# Mirror_Schematic.net
KiCad netlist of a schematic drawn in Altium Designer
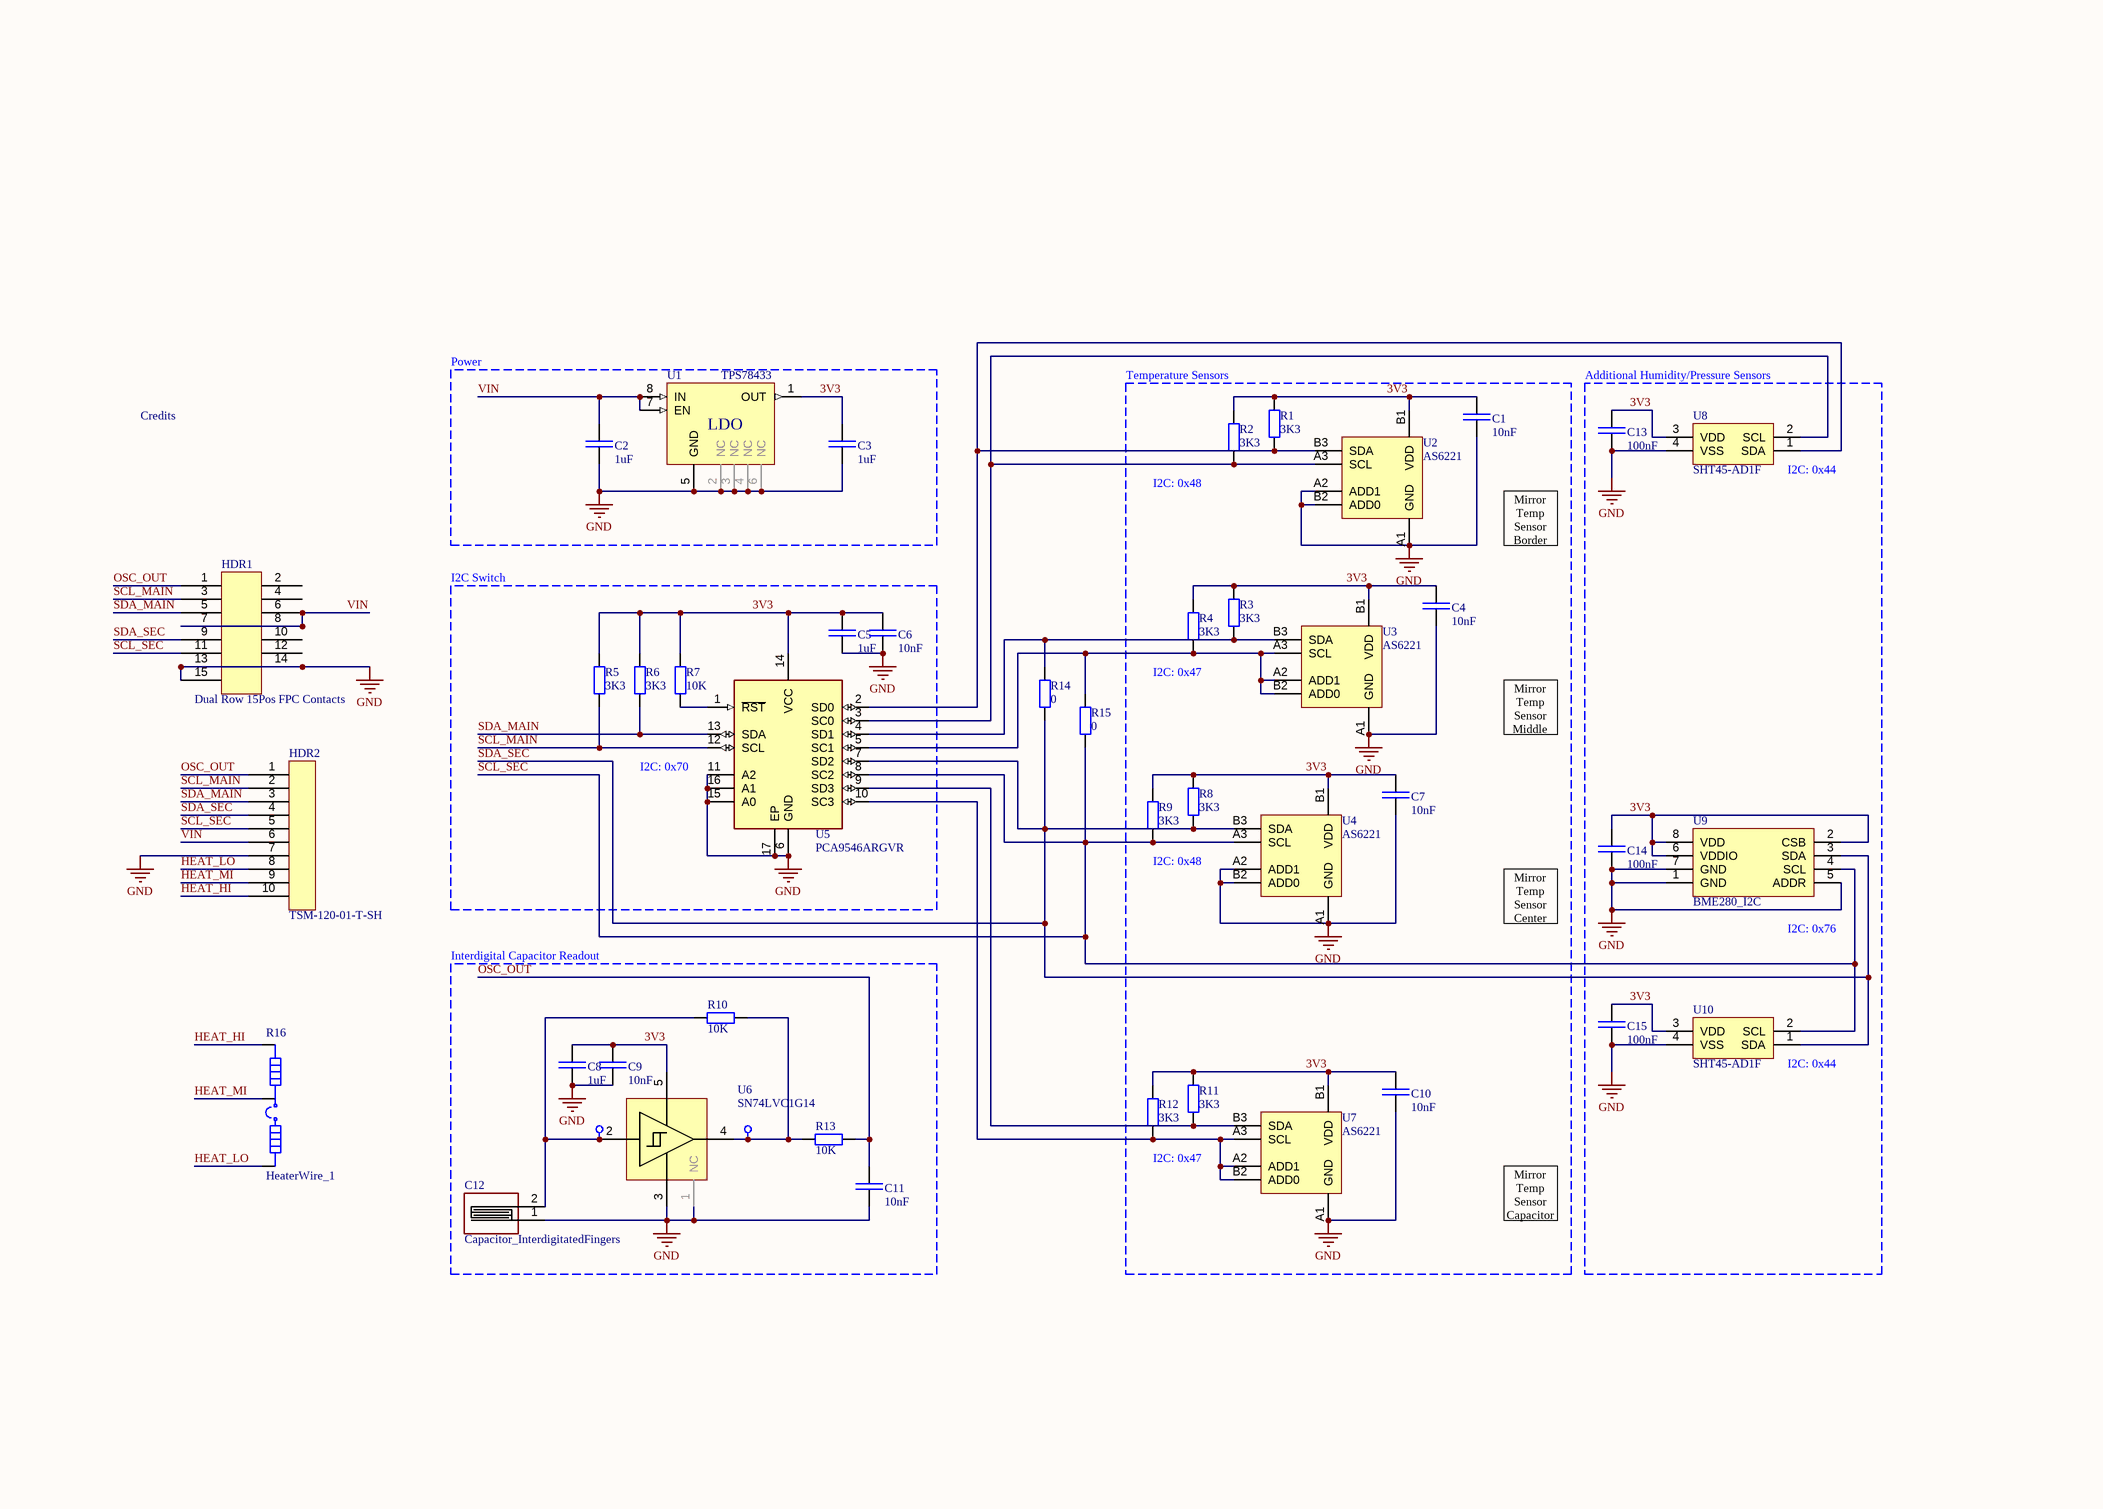
[diagram p0: Mirror_Schematic.SchDoc]

(export (version "E")
  (design (tool "Eeschema 10.0.6"))
  (components
    (comp (ref "C1")
      (value "10nF")
      (footprint "CAP_SM0402_YAGEOCC2_N")
      (description "CAP 10nF SM0402 X7R 50V YAGEO CC2")
      (fields
        (field (name "MANUFACTURER") "Yageo")
        (field (name "MANUFACTURER PART NUMBER") "CC0603KRX7R9BB103")
      )
      (libsource (lib "Mirror_Symbols") (part "CC0402KRX7R9BB103"))
    )
    (comp (ref "C2")
      (value "1uF")
      (footprint "CAP_SM0805_YAGEOCC2_N")
      (description "CAP 1uF SM0805 X7R 25V YAGEO CC2")
      (fields
        (field (name "MANUFACTURER") "Yageo")
        (field (name "MANUFACTURER PART NUMBER") "CC0805KKX7R8BB105")
      )
      (libsource (lib "Mirror_Symbols") (part "CC0805KKX7R8BB105"))
    )
    (comp (ref "C3")
      (value "1uF")
      (footprint "CAP_SM0805_YAGEOCC2_N")
      (description "CAP 1uF SM0805 X7R 25V YAGEO CC2")
      (fields
        (field (name "MANUFACTURER") "Yageo")
        (field (name "MANUFACTURER PART NUMBER") "CC0805KKX7R8BB105")
      )
      (libsource (lib "Mirror_Symbols") (part "CC0805KKX7R8BB105"))
    )
    (comp (ref "C4")
      (value "10nF")
      (footprint "CAP_SM0402_YAGEOCC2_N")
      (description "CAP 10nF SM0402 X7R 50V YAGEO CC2")
      (fields
        (field (name "MANUFACTURER") "Yageo")
        (field (name "MANUFACTURER PART NUMBER") "CC0603KRX7R9BB103")
      )
      (libsource (lib "Mirror_Symbols") (part "CC0402KRX7R9BB103"))
    )
    (comp (ref "C5")
      (value "1uF")
      (footprint "CAP_SM0805_YAGEOCC2_N")
      (description "CAP 1uF SM0805 X7R 25V YAGEO CC2")
      (fields
        (field (name "MANUFACTURER") "Yageo")
        (field (name "MANUFACTURER PART NUMBER") "CC0805KKX7R8BB105")
      )
      (libsource (lib "Mirror_Symbols") (part "CC0805KKX7R8BB105"))
    )
    (comp (ref "C6")
      (value "10nF")
      (footprint "CAP_SM0402_YAGEOCC2_N")
      (description "CAP 10nF SM0402 X7R 50V YAGEO CC2")
      (fields
        (field (name "MANUFACTURER") "Yageo")
        (field (name "MANUFACTURER PART NUMBER") "CC0603KRX7R9BB103")
      )
      (libsource (lib "Mirror_Symbols") (part "CC0402KRX7R9BB103"))
    )
    (comp (ref "C7")
      (value "10nF")
      (footprint "CAP_SM0402_YAGEOCC2_N")
      (description "CAP 10nF SM0402 X7R 50V YAGEO CC2")
      (fields
        (field (name "MANUFACTURER") "Yageo")
        (field (name "MANUFACTURER PART NUMBER") "CC0603KRX7R9BB103")
      )
      (libsource (lib "Mirror_Symbols") (part "CC0402KRX7R9BB103"))
    )
    (comp (ref "C8")
      (value "1uF")
      (footprint "CAP_SM0805_YAGEOCC2_N")
      (description "CAP 1uF SM0805 X7R 25V YAGEO CC2")
      (fields
        (field (name "MANUFACTURER") "Yageo")
        (field (name "MANUFACTURER PART NUMBER") "CC0805KKX7R8BB105")
      )
      (libsource (lib "Mirror_Symbols") (part "CC0805KKX7R8BB105"))
    )
    (comp (ref "C9")
      (value "10nF")
      (footprint "CAP_SM0603_YAGEOCC2_N")
      (description "CAP 10nF SM0603 X7R 50V YAGEO CC2")
      (fields
        (field (name "MANUFACTURER") "Yageo")
        (field (name "MANUFACTURER PART NUMBER") "CC0603KRX7R9BB103")
      )
      (libsource (lib "Mirror_Symbols") (part "CC0603KRX7R9BB103"))
    )
    (comp (ref "C10")
      (value "10nF")
      (footprint "CAP_SM0402_YAGEOCC2_N")
      (description "CAP 10nF SM0402 X7R 50V YAGEO CC2")
      (fields
        (field (name "MANUFACTURER") "Yageo")
        (field (name "MANUFACTURER PART NUMBER") "CC0603KRX7R9BB103")
      )
      (libsource (lib "Mirror_Symbols") (part "CC0402KRX7R9BB103"))
    )
    (comp (ref "C11")
      (value "10nF")
      (footprint "CAP_SM0603_YAGEOCC2_N")
      (description "CAP 10nF SM0603 X7R 50V YAGEO CC2")
      (fields
        (field (name "MANUFACTURER") "Yageo")
        (field (name "MANUFACTURER PART NUMBER") "CC0603KRX7R9BB103")
      )
      (libsource (lib "Mirror_Symbols") (part "CC0603KRX7R9BB103"))
    )
    (comp (ref "C12")
      (value "Capacitor_InterdigitatedFingers")
      (footprint "CapacitorWire")
      (libsource (lib "Mirror_Symbols") (part "Capacitor_InterdigitatedFingers"))
    )
    (comp (ref "C13")
      (value "100nF")
      (footprint "CAP_SM0603_YAGEOCC2_N")
      (description "CAP 100nF SM0603 X7R 50V YAGEO CC2")
      (fields
        (field (name "MANUFACTURER") "Yageo")
        (field (name "MANUFACTURER PART NUMBER") "CC0603KRX7R9BB104")
      )
      (libsource (lib "Mirror_Symbols") (part "CC0603KRX7R9BB104"))
    )
    (comp (ref "C14")
      (value "100nF")
      (footprint "CAP_SM0603_YAGEOCC2_N")
      (description "CAP 100nF SM0603 X7R 50V YAGEO CC2")
      (fields
        (field (name "MANUFACTURER") "Yageo")
        (field (name "MANUFACTURER PART NUMBER") "CC0603KRX7R9BB104")
      )
      (libsource (lib "Mirror_Symbols") (part "CC0603KRX7R9BB104"))
    )
    (comp (ref "C15")
      (value "100nF")
      (footprint "CAP_SM0603_YAGEOCC2_N")
      (description "CAP 100nF SM0603 X7R 50V YAGEO CC2")
      (fields
        (field (name "MANUFACTURER") "Yageo")
        (field (name "MANUFACTURER PART NUMBER") "CC0603KRX7R9BB104")
      )
      (libsource (lib "Mirror_Symbols") (part "CC0603KRX7R9BB104"))
    )
    (comp (ref "Credit")
      (value "Credits")
      (footprint "CREDITS_CU_SIGNED")
      (libsource (lib "Mirror_Symbols") (part "Credits"))
    )
    (comp (ref "HDR1")
      (value "Dual Row 15Pos FPC Contacts")
      (footprint "AYF331535_FPC")
      (libsource (lib "Mirror_Symbols") (part "FPC_Contacts_15_DualRow"))
    )
    (comp (ref "HDR2")
      (value "TSM-120-01-T-SH")
      (footprint "TSM-120-01-T-SH")
      (description "SURFACE MOUNT (2.54 mm) .100\" PITCH .025\" SQ POST HEADER")
      (libsource (lib "Mirror_Symbols") (part "TSM-120-01-T-SH"))
    )
    (comp (ref "J4")
      (value "S1751-46 TestPoint")
      (footprint "S1751-46 TestPoint")
      (description "S1751-46 SMT TestPoint 3.25x1.65")
      (libsource (lib "Mirror_Symbols") (part "S1751-46 TestPoint"))
    )
    (comp (ref "J5")
      (value "S1751-46 TestPoint")
      (footprint "S1751-46 TestPoint")
      (description "S1751-46 SMT TestPoint 3.25x1.65")
      (libsource (lib "Mirror_Symbols") (part "S1751-46 TestPoint"))
    )
    (comp (ref "R1")
      (value "3K3")
      (footprint "RES_SM0603_YAGEORC_N")
      (description "RES 3K3 SM0603 YAGEO RC_L")
      (fields
        (field (name "MANUFACTURER") "Yageo")
        (field (name "MANUFACTURER PART NUMBER") "RC0603FR-0710KL")
      )
      (libsource (lib "Mirror_Symbols") (part "RC0603FR-073K3L"))
    )
    (comp (ref "R2")
      (value "3K3")
      (footprint "RES_SM0603_YAGEORC_N")
      (description "RES 3K3 SM0603 YAGEO RC_L")
      (fields
        (field (name "MANUFACTURER") "Yageo")
        (field (name "MANUFACTURER PART NUMBER") "RC0603FR-0710KL")
      )
      (libsource (lib "Mirror_Symbols") (part "RC0603FR-073K3L"))
    )
    (comp (ref "R3")
      (value "3K3")
      (footprint "RES_SM0603_YAGEORC_N")
      (description "RES 3K3 SM0603 YAGEO RC_L")
      (fields
        (field (name "MANUFACTURER") "Yageo")
        (field (name "MANUFACTURER PART NUMBER") "RC0603FR-0710KL")
      )
      (libsource (lib "Mirror_Symbols") (part "RC0603FR-073K3L"))
    )
    (comp (ref "R4")
      (value "3K3")
      (footprint "RES_SM0603_YAGEORC_N")
      (description "RES 3K3 SM0603 YAGEO RC_L")
      (fields
        (field (name "MANUFACTURER") "Yageo")
        (field (name "MANUFACTURER PART NUMBER") "RC0603FR-0710KL")
      )
      (libsource (lib "Mirror_Symbols") (part "RC0603FR-073K3L"))
    )
    (comp (ref "R5")
      (value "3K3")
      (footprint "RES_SM0603_YAGEORC_N")
      (description "RES 3K3 SM0603 YAGEO RC_L")
      (fields
        (field (name "MANUFACTURER") "Yageo")
        (field (name "MANUFACTURER PART NUMBER") "RC0603FR-0710KL")
      )
      (libsource (lib "") (part "RC0603FR-073K3L_1"))
    )
    (comp (ref "R6")
      (value "3K3")
      (footprint "RES_SM0603_YAGEORC_N")
      (description "RES 3K3 SM0603 YAGEO RC_L")
      (fields
        (field (name "MANUFACTURER") "Yageo")
        (field (name "MANUFACTURER PART NUMBER") "RC0603FR-0710KL")
      )
      (libsource (lib "") (part "RC0603FR-073K3L_1"))
    )
    (comp (ref "R7")
      (value "10K")
      (footprint "RES_SM0603_YAGEORC_N")
      (description "RES 10K SM0603 YAGEO RC_L")
      (fields
        (field (name "MANUFACTURER") "Yageo")
        (field (name "MANUFACTURER PART NUMBER") "RC0603FR-0710KL")
      )
      (libsource (lib "") (part "RC0603FR-0710KL_1"))
    )
    (comp (ref "R8")
      (value "3K3")
      (footprint "RES_SM0603_YAGEORC_N")
      (description "RES 3K3 SM0603 YAGEO RC_L")
      (fields
        (field (name "MANUFACTURER") "Yageo")
        (field (name "MANUFACTURER PART NUMBER") "RC0603FR-0710KL")
      )
      (libsource (lib "Mirror_Symbols") (part "RC0603FR-073K3L"))
    )
    (comp (ref "R9")
      (value "3K3")
      (footprint "RES_SM0603_YAGEORC_N")
      (description "RES 3K3 SM0603 YAGEO RC_L")
      (fields
        (field (name "MANUFACTURER") "Yageo")
        (field (name "MANUFACTURER PART NUMBER") "RC0603FR-0710KL")
      )
      (libsource (lib "Mirror_Symbols") (part "RC0603FR-073K3L"))
    )
    (comp (ref "R10")
      (value "10K")
      (footprint "RES_SM0603_YAGEORC_N")
      (description "RES 10K SM0603 YAGEO RC_L")
      (fields
        (field (name "MANUFACTURER") "Yageo")
        (field (name "MANUFACTURER PART NUMBER") "RC0603FR-0710KL")
      )
      (libsource (lib "Mirror_Symbols") (part "RC0603FR-0710KL"))
    )
    (comp (ref "R11")
      (value "3K3")
      (footprint "RES_SM0603_YAGEORC_N")
      (description "RES 3K3 SM0603 YAGEO RC_L")
      (fields
        (field (name "MANUFACTURER") "Yageo")
        (field (name "MANUFACTURER PART NUMBER") "RC0603FR-0710KL")
      )
      (libsource (lib "Mirror_Symbols") (part "RC0603FR-073K3L"))
    )
    (comp (ref "R12")
      (value "3K3")
      (footprint "RES_SM0603_YAGEORC_N")
      (description "RES 3K3 SM0603 YAGEO RC_L")
      (fields
        (field (name "MANUFACTURER") "Yageo")
        (field (name "MANUFACTURER PART NUMBER") "RC0603FR-0710KL")
      )
      (libsource (lib "Mirror_Symbols") (part "RC0603FR-073K3L"))
    )
    (comp (ref "R13")
      (value "10K")
      (footprint "RES_SM0603_YAGEORC_N")
      (description "RES 10K SM0603 YAGEO RC_L")
      (fields
        (field (name "MANUFACTURER") "Yageo")
        (field (name "MANUFACTURER PART NUMBER") "RC0603FR-0710KL")
      )
      (libsource (lib "Mirror_Symbols") (part "RC0603FR-0710KL"))
    )
    (comp (ref "R14")
      (value "0")
      (footprint "RES_SM0603_YAGEORC_N")
      (description "RES 0R SM0603 YAGEO RC_L")
      (fields
        (field (name "MANUFACTURER") "Yageo")
        (field (name "MANUFACTURER PART NUMBER") "RC0603FR-0710KL")
      )
      (libsource (lib "Mirror_Symbols") (part "RC0603FR-070RL"))
    )
    (comp (ref "R15")
      (value "0")
      (footprint "RES_SM0603_YAGEORC_N")
      (description "RES 0R SM0603 YAGEO RC_L")
      (fields
        (field (name "MANUFACTURER") "Yageo")
        (field (name "MANUFACTURER PART NUMBER") "RC0603FR-0710KL")
      )
      (libsource (lib "Mirror_Symbols") (part "RC0603FR-070RL"))
    )
    (comp (ref "R16")
      (value "HeaterWire_1")
      (footprint "HeaterWire_1")
      (libsource (lib "Mirror_Symbols") (part "HeaterWire_1"))
    )
    (comp (ref "U1")
      (value "TPS78433")
      (footprint "TPS784xxxQDRBRQ1_SON")
      (libsource (lib "Mirror_Symbols") (part "TPS78433QWDRBRQ1"))
    )
    (comp (ref "U2")
      (value "AS6221")
      (footprint "AS6221_BGA_LargePads")
      (description "AS6221 Temperature Sensor Digital -40°C ~ 125°C 16b 6-WLCSP (1.5x1.03)")
      (libsource (lib "Mirror_Symbols") (part "AS6221-AWLT-S"))
    )
    (comp (ref "U3")
      (value "AS6221")
      (footprint "AS6221_BGA_LargePads")
      (description "AS6221 Temperature Sensor Digital -40°C ~ 125°C 16b 6-WLCSP (1.5x1.03)")
      (libsource (lib "Mirror_Symbols") (part "AS6221-AWLT-S"))
    )
    (comp (ref "U4")
      (value "AS6221")
      (footprint "AS6221_BGA_LargePads")
      (description "AS6221 Temperature Sensor Digital -40°C ~ 125°C 16b 6-WLCSP (1.5x1.03)")
      (libsource (lib "Mirror_Symbols") (part "AS6221-AWLT-S"))
    )
    (comp (ref "U5")
      (value "PCA9546ARGVR")
      (footprint "QFN65P400X400X100-17N-D")
      (description "4-Channel I2C And SMBus Switch With Reset Functions")
      (fields (field (name "MOUSER PART NUMBER") "595-PCA9546ARGVR"))
      (libsource (lib "Mirror_Symbols") (part "PCA9546ARGVR"))
    )
    (comp (ref "U6")
      (value "SN74LVC1G14")
      (footprint "SOT65P210X110-5N_SC70")
      (libsource (lib "Mirror_Symbols") (part "SN74LVC1G14"))
    )
    (comp (ref "U7")
      (value "AS6221")
      (footprint "AS6221_BGA_LargePads")
      (description "AS6221 Temperature Sensor Digital -40°C ~ 125°C 16b 6-WLCSP (1.5x1.03)")
      (libsource (lib "Mirror_Symbols") (part "AS6221-AWLT-S"))
    )
    (comp (ref "U8")
      (value "SHT45-AD1F")
      (footprint "SHT45 DFN")
      (description "SHT45 4th Gen. High-Accuracy, Ultra-Low-Power, 16-bit, Relative Humidity and Temperature Sensor")
      (libsource (lib "Mirror_Symbols") (part "SHT45-AD1F"))
    )
    (comp (ref "U9")
      (value "BME280_I2C")
      (footprint "BME280")
      (description "BME280 Digital humidity, pressure and temperature sensor")
      (libsource (lib "Mirror_Symbols") (part "BME280_I2C"))
    )
    (comp (ref "U10")
      (value "SHT45-AD1F")
      (footprint "SHT45 DFN")
      (description "SHT45 4th Gen. High-Accuracy, Ultra-Low-Power, 16-bit, Relative Humidity and Temperature Sensor")
      (libsource (lib "Mirror_Symbols") (part "SHT45-AD1F"))
    )
  )
  (nets
    (net (code "1") (name "/3V3") (class "Default")
      (node (ref "C1") (pin "1") (pintype "passive"))
      (node (ref "C10") (pin "1") (pintype "passive"))
      (node (ref "C13") (pin "1") (pintype "passive"))
      (node (ref "C14") (pin "1") (pintype "passive"))
      (node (ref "C15") (pin "1") (pintype "passive"))
      (node (ref "C3") (pin "1") (pintype "passive"))
      (node (ref "C4") (pin "1") (pintype "passive"))
      (node (ref "C5") (pin "1") (pintype "passive"))
      (node (ref "C6") (pin "1") (pintype "passive"))
      (node (ref "C7") (pin "1") (pintype "passive"))
      (node (ref "C8") (pin "1") (pintype "passive"))
      (node (ref "C9") (pin "1") (pintype "passive"))
      (node (ref "R1") (pin "2") (pintype "passive"))
      (node (ref "R11") (pin "2") (pintype "passive"))
      (node (ref "R12") (pin "2") (pintype "passive"))
      (node (ref "R2") (pin "2") (pintype "passive"))
      (node (ref "R3") (pin "2") (pintype "passive"))
      (node (ref "R4") (pin "2") (pintype "passive"))
      (node (ref "R5") (pin "1") (pintype "passive"))
      (node (ref "R6") (pin "1") (pintype "passive"))
      (node (ref "R7") (pin "1") (pintype "passive"))
      (node (ref "R8") (pin "2") (pintype "passive"))
      (node (ref "R9") (pin "2") (pintype "passive"))
      (node (ref "U1") (pin "1") (pinfunction "OUT_1") (pintype "output"))
      (node (ref "U10") (pin "3") (pinfunction "VDD_3") (pintype "passive"))
      (node (ref "U2") (pin "B1") (pinfunction "VDD_B1") (pintype "passive"))
      (node (ref "U3") (pin "B1") (pinfunction "VDD_B1") (pintype "passive"))
      (node (ref "U4") (pin "B1") (pinfunction "VDD_B1") (pintype "passive"))
      (node (ref "U5") (pin "14") (pinfunction "VCC_14") (pintype "passive"))
      (node (ref "U6") (pin "5") (pinfunction "VCC_5") (pintype "passive"))
      (node (ref "U7") (pin "B1") (pinfunction "VDD_B1") (pintype "passive"))
      (node (ref "U8") (pin "3") (pinfunction "VDD_3") (pintype "passive"))
      (node (ref "U9") (pin "2") (pinfunction "CSB_2") (pintype "passive"))
      (node (ref "U9") (pin "6") (pinfunction "VDDIO_6") (pintype "passive"))
      (node (ref "U9") (pin "8") (pinfunction "VDD_8") (pintype "passive"))
    )
    (net (code "2") (name "/HEAT_HI") (class "Default")
      (node (ref "HDR2") (pin "10") (pintype "passive"))
      (node (ref "R16") (pin "1") (pintype "passive"))
    )
    (net (code "3") (name "/HEAT_LO") (class "Default")
      (node (ref "HDR2") (pin "8") (pintype "passive"))
      (node (ref "R16") (pin "3") (pintype "passive"))
    )
    (net (code "4") (name "/HEAT_MI") (class "Default")
      (node (ref "HDR2") (pin "9") (pintype "passive"))
      (node (ref "R16") (pin "2") (pintype "passive"))
    )
    (net (code "5") (name "/OSC_OUT") (class "Default")
      (node (ref "C11") (pin "1") (pintype "passive"))
      (node (ref "HDR1") (pin "1") (pintype "passive"))
      (node (ref "HDR2") (pin "1") (pintype "passive"))
      (node (ref "R13") (pin "1") (pintype "passive"))
    )
    (net (code "6") (name "/SCL_MAIN") (class "Default")
      (node (ref "HDR1") (pin "3") (pintype "passive"))
      (node (ref "HDR2") (pin "2") (pintype "passive"))
      (node (ref "R5") (pin "2") (pintype "passive"))
      (node (ref "U5") (pin "12") (pinfunction "SCL_12") (pintype "bidirectional"))
    )
    (net (code "7") (name "/SCL_SEC") (class "Default")
      (node (ref "HDR1") (pin "11") (pintype "passive"))
      (node (ref "HDR2") (pin "5") (pintype "passive"))
      (node (ref "R15") (pin "1") (pintype "passive"))
      (node (ref "R9") (pin "1") (pintype "passive"))
      (node (ref "U10") (pin "2") (pinfunction "SCL_2") (pintype "passive"))
      (node (ref "U4") (pin "A3") (pinfunction "SCL_A3") (pintype "passive"))
      (node (ref "U5") (pin "8") (pinfunction "SC2_8") (pintype "bidirectional"))
      (node (ref "U9") (pin "4") (pinfunction "SCL_4") (pintype "passive"))
    )
    (net (code "8") (name "/SDA_MAIN") (class "Default")
      (node (ref "HDR1") (pin "5") (pintype "passive"))
      (node (ref "HDR2") (pin "3") (pintype "passive"))
      (node (ref "R6") (pin "2") (pintype "passive"))
      (node (ref "U5") (pin "13") (pinfunction "SDA_13") (pintype "bidirectional"))
    )
    (net (code "9") (name "/SDA_SEC") (class "Default")
      (node (ref "HDR1") (pin "9") (pintype "passive"))
      (node (ref "HDR2") (pin "4") (pintype "passive"))
      (node (ref "R14") (pin "1") (pintype "passive"))
      (node (ref "R8") (pin "1") (pintype "passive"))
      (node (ref "U10") (pin "1") (pinfunction "SDA_1") (pintype "passive"))
      (node (ref "U4") (pin "B3") (pinfunction "SDA_B3") (pintype "passive"))
      (node (ref "U5") (pin "7") (pinfunction "SD2_7") (pintype "bidirectional"))
      (node (ref "U9") (pin "3") (pinfunction "SDA_3") (pintype "passive"))
    )
    (net (code "10") (name "/VIN") (class "Default")
      (node (ref "C2") (pin "1") (pintype "passive"))
      (node (ref "HDR1") (pin "6") (pintype "passive"))
      (node (ref "HDR1") (pin "7") (pintype "passive"))
      (node (ref "HDR1") (pin "8") (pintype "passive"))
      (node (ref "HDR2") (pin "6") (pintype "passive"))
      (node (ref "U1") (pin "7") (pinfunction "EN_7") (pintype "input"))
      (node (ref "U1") (pin "8") (pinfunction "IN_8") (pintype "input"))
    )
    (net (code "11") (name "GND") (class "Default")
      (node (ref "C1") (pin "2") (pintype "passive"))
      (node (ref "C10") (pin "2") (pintype "passive"))
      (node (ref "C11") (pin "2") (pintype "passive"))
      (node (ref "C12") (pin "1") (pintype "passive"))
      (node (ref "C13") (pin "2") (pintype "passive"))
      (node (ref "C14") (pin "2") (pintype "passive"))
      (node (ref "C15") (pin "2") (pintype "passive"))
      (node (ref "C2") (pin "2") (pintype "passive"))
      (node (ref "C3") (pin "2") (pintype "passive"))
      (node (ref "C4") (pin "2") (pintype "passive"))
      (node (ref "C5") (pin "2") (pintype "passive"))
      (node (ref "C6") (pin "2") (pintype "passive"))
      (node (ref "C7") (pin "2") (pintype "passive"))
      (node (ref "C8") (pin "2") (pintype "passive"))
      (node (ref "C9") (pin "2") (pintype "passive"))
      (node (ref "HDR1") (pin "13") (pintype "passive"))
      (node (ref "HDR1") (pin "14") (pintype "passive"))
      (node (ref "HDR1") (pin "15") (pintype "passive"))
      (node (ref "HDR2") (pin "7") (pintype "passive"))
      (node (ref "U1") (pin "2") (pinfunction "NC_2") (pintype "passive"))
      (node (ref "U1") (pin "3") (pinfunction "NC_3") (pintype "passive"))
      (node (ref "U1") (pin "4") (pinfunction "NC_4") (pintype "passive"))
      (node (ref "U1") (pin "5") (pinfunction "GND_5") (pintype "passive"))
      (node (ref "U1") (pin "6") (pinfunction "NC_6") (pintype "passive"))
      (node (ref "U10") (pin "4") (pinfunction "VSS_4") (pintype "passive"))
      (node (ref "U2") (pin "A1") (pinfunction "GND_A1") (pintype "passive"))
      (node (ref "U2") (pin "A2") (pinfunction "ADD1_A2") (pintype "passive"))
      (node (ref "U2") (pin "B2") (pinfunction "ADD0_B2") (pintype "passive"))
      (node (ref "U3") (pin "A1") (pinfunction "GND_A1") (pintype "passive"))
      (node (ref "U4") (pin "A1") (pinfunction "GND_A1") (pintype "passive"))
      (node (ref "U4") (pin "A2") (pinfunction "ADD1_A2") (pintype "passive"))
      (node (ref "U4") (pin "B2") (pinfunction "ADD0_B2") (pintype "passive"))
      (node (ref "U5") (pin "11") (pinfunction "A2_11") (pintype "passive"))
      (node (ref "U5") (pin "15") (pinfunction "A0_15") (pintype "passive"))
      (node (ref "U5") (pin "16") (pinfunction "A1_16") (pintype "passive"))
      (node (ref "U5") (pin "17") (pinfunction "EP_17") (pintype "passive"))
      (node (ref "U5") (pin "6") (pinfunction "GND_6") (pintype "passive"))
      (node (ref "U6") (pin "1") (pinfunction "NC_1") (pintype "passive"))
      (node (ref "U6") (pin "3") (pinfunction "57_3") (pintype "passive"))
      (node (ref "U7") (pin "A1") (pinfunction "GND_A1") (pintype "passive"))
      (node (ref "U8") (pin "4") (pinfunction "VSS_4") (pintype "passive"))
      (node (ref "U9") (pin "1") (pinfunction "GND_1") (pintype "passive"))
      (node (ref "U9") (pin "5") (pinfunction "ADDR_5") (pintype "passive"))
      (node (ref "U9") (pin "7") (pinfunction "GND_7") (pintype "passive"))
    )
    (net (code "12") (name "Net-(U2-SCL)") (class "Default")
      (node (ref "R2") (pin "1") (pintype "passive"))
      (node (ref "U2") (pin "A3") (pinfunction "SCL_A3") (pintype "passive"))
      (node (ref "U5") (pin "3") (pinfunction "SC0_3") (pintype "bidirectional"))
      (node (ref "U8") (pin "2") (pinfunction "SCL_2") (pintype "passive"))
    )
    (net (code "13") (name "Net-(U2-SDA)") (class "Default")
      (node (ref "R1") (pin "1") (pintype "passive"))
      (node (ref "U2") (pin "B3") (pinfunction "SDA_B3") (pintype "passive"))
      (node (ref "U5") (pin "2") (pinfunction "SD0_2") (pintype "bidirectional"))
      (node (ref "U8") (pin "1") (pinfunction "SDA_1") (pintype "passive"))
    )
    (net (code "14") (name "Net-(U3-ADD0)") (class "Default")
      (node (ref "R15") (pin "2") (pintype "passive"))
      (node (ref "R4") (pin "1") (pintype "passive"))
      (node (ref "U3") (pin "A2") (pinfunction "ADD1_A2") (pintype "passive"))
      (node (ref "U3") (pin "A3") (pinfunction "SCL_A3") (pintype "passive"))
      (node (ref "U3") (pin "B2") (pinfunction "ADD0_B2") (pintype "passive"))
      (node (ref "U5") (pin "5") (pinfunction "SC1_5") (pintype "bidirectional"))
    )
    (net (code "15") (name "Net-(U3-SDA)") (class "Default")
      (node (ref "R14") (pin "2") (pintype "passive"))
      (node (ref "R3") (pin "1") (pintype "passive"))
      (node (ref "U3") (pin "B3") (pinfunction "SDA_B3") (pintype "passive"))
      (node (ref "U5") (pin "4") (pinfunction "SD1_4") (pintype "bidirectional"))
    )
    (net (code "16") (name "Net-(U5-SC3)") (class "Default")
      (node (ref "R12") (pin "1") (pintype "passive"))
      (node (ref "U5") (pin "10") (pinfunction "SC3_10") (pintype "bidirectional"))
      (node (ref "U7") (pin "A2") (pinfunction "ADD1_A2") (pintype "passive"))
      (node (ref "U7") (pin "A3") (pinfunction "SCL_A3") (pintype "passive"))
      (node (ref "U7") (pin "B2") (pinfunction "ADD0_B2") (pintype "passive"))
    )
    (net (code "17") (name "Net-(U5-SD3)") (class "Default")
      (node (ref "R11") (pin "1") (pintype "passive"))
      (node (ref "U5") (pin "9") (pinfunction "SD3_9") (pintype "bidirectional"))
      (node (ref "U7") (pin "B3") (pinfunction "SDA_B3") (pintype "passive"))
    )
    (net (code "18") (name "Net-(U5-~{RST})") (class "Default")
      (node (ref "R7") (pin "2") (pintype "passive"))
      (node (ref "U5") (pin "1") (pinfunction "~{RST}_1") (pintype "input"))
    )
    (net (code "19") (name "Net-(U6-A)") (class "Default")
      (node (ref "C12") (pin "2") (pintype "passive"))
      (node (ref "J4") (pin "1") (pintype "passive"))
      (node (ref "R10") (pin "2") (pintype "passive"))
      (node (ref "U6") (pin "2") (pinfunction "A_2") (pintype "passive"))
    )
    (net (code "20") (name "Net-(U6-Y)") (class "Default")
      (node (ref "J5") (pin "1") (pintype "passive"))
      (node (ref "R10") (pin "1") (pintype "passive"))
      (node (ref "R13") (pin "2") (pintype "passive"))
      (node (ref "U6") (pin "4") (pinfunction "Y_4") (pintype "passive"))
    )
    (net (code "21") (name "unconnected-(HDR1-Pad2)") (class "Default")
      (node (ref "HDR1") (pin "2") (pintype "passive"))
    )
    (net (code "22") (name "unconnected-(HDR1-Pad4)") (class "Default")
      (node (ref "HDR1") (pin "4") (pintype "passive"))
    )
    (net (code "23") (name "unconnected-(HDR1-Pad10)") (class "Default")
      (node (ref "HDR1") (pin "10") (pintype "passive"))
    )
    (net (code "24") (name "unconnected-(HDR1-Pad12)") (class "Default")
      (node (ref "HDR1") (pin "12") (pintype "passive"))
    )
  )
)
